# ETR_CELLMETER_SLAVE.net
KiCad netlist of a schematic drawn in Altium Designer
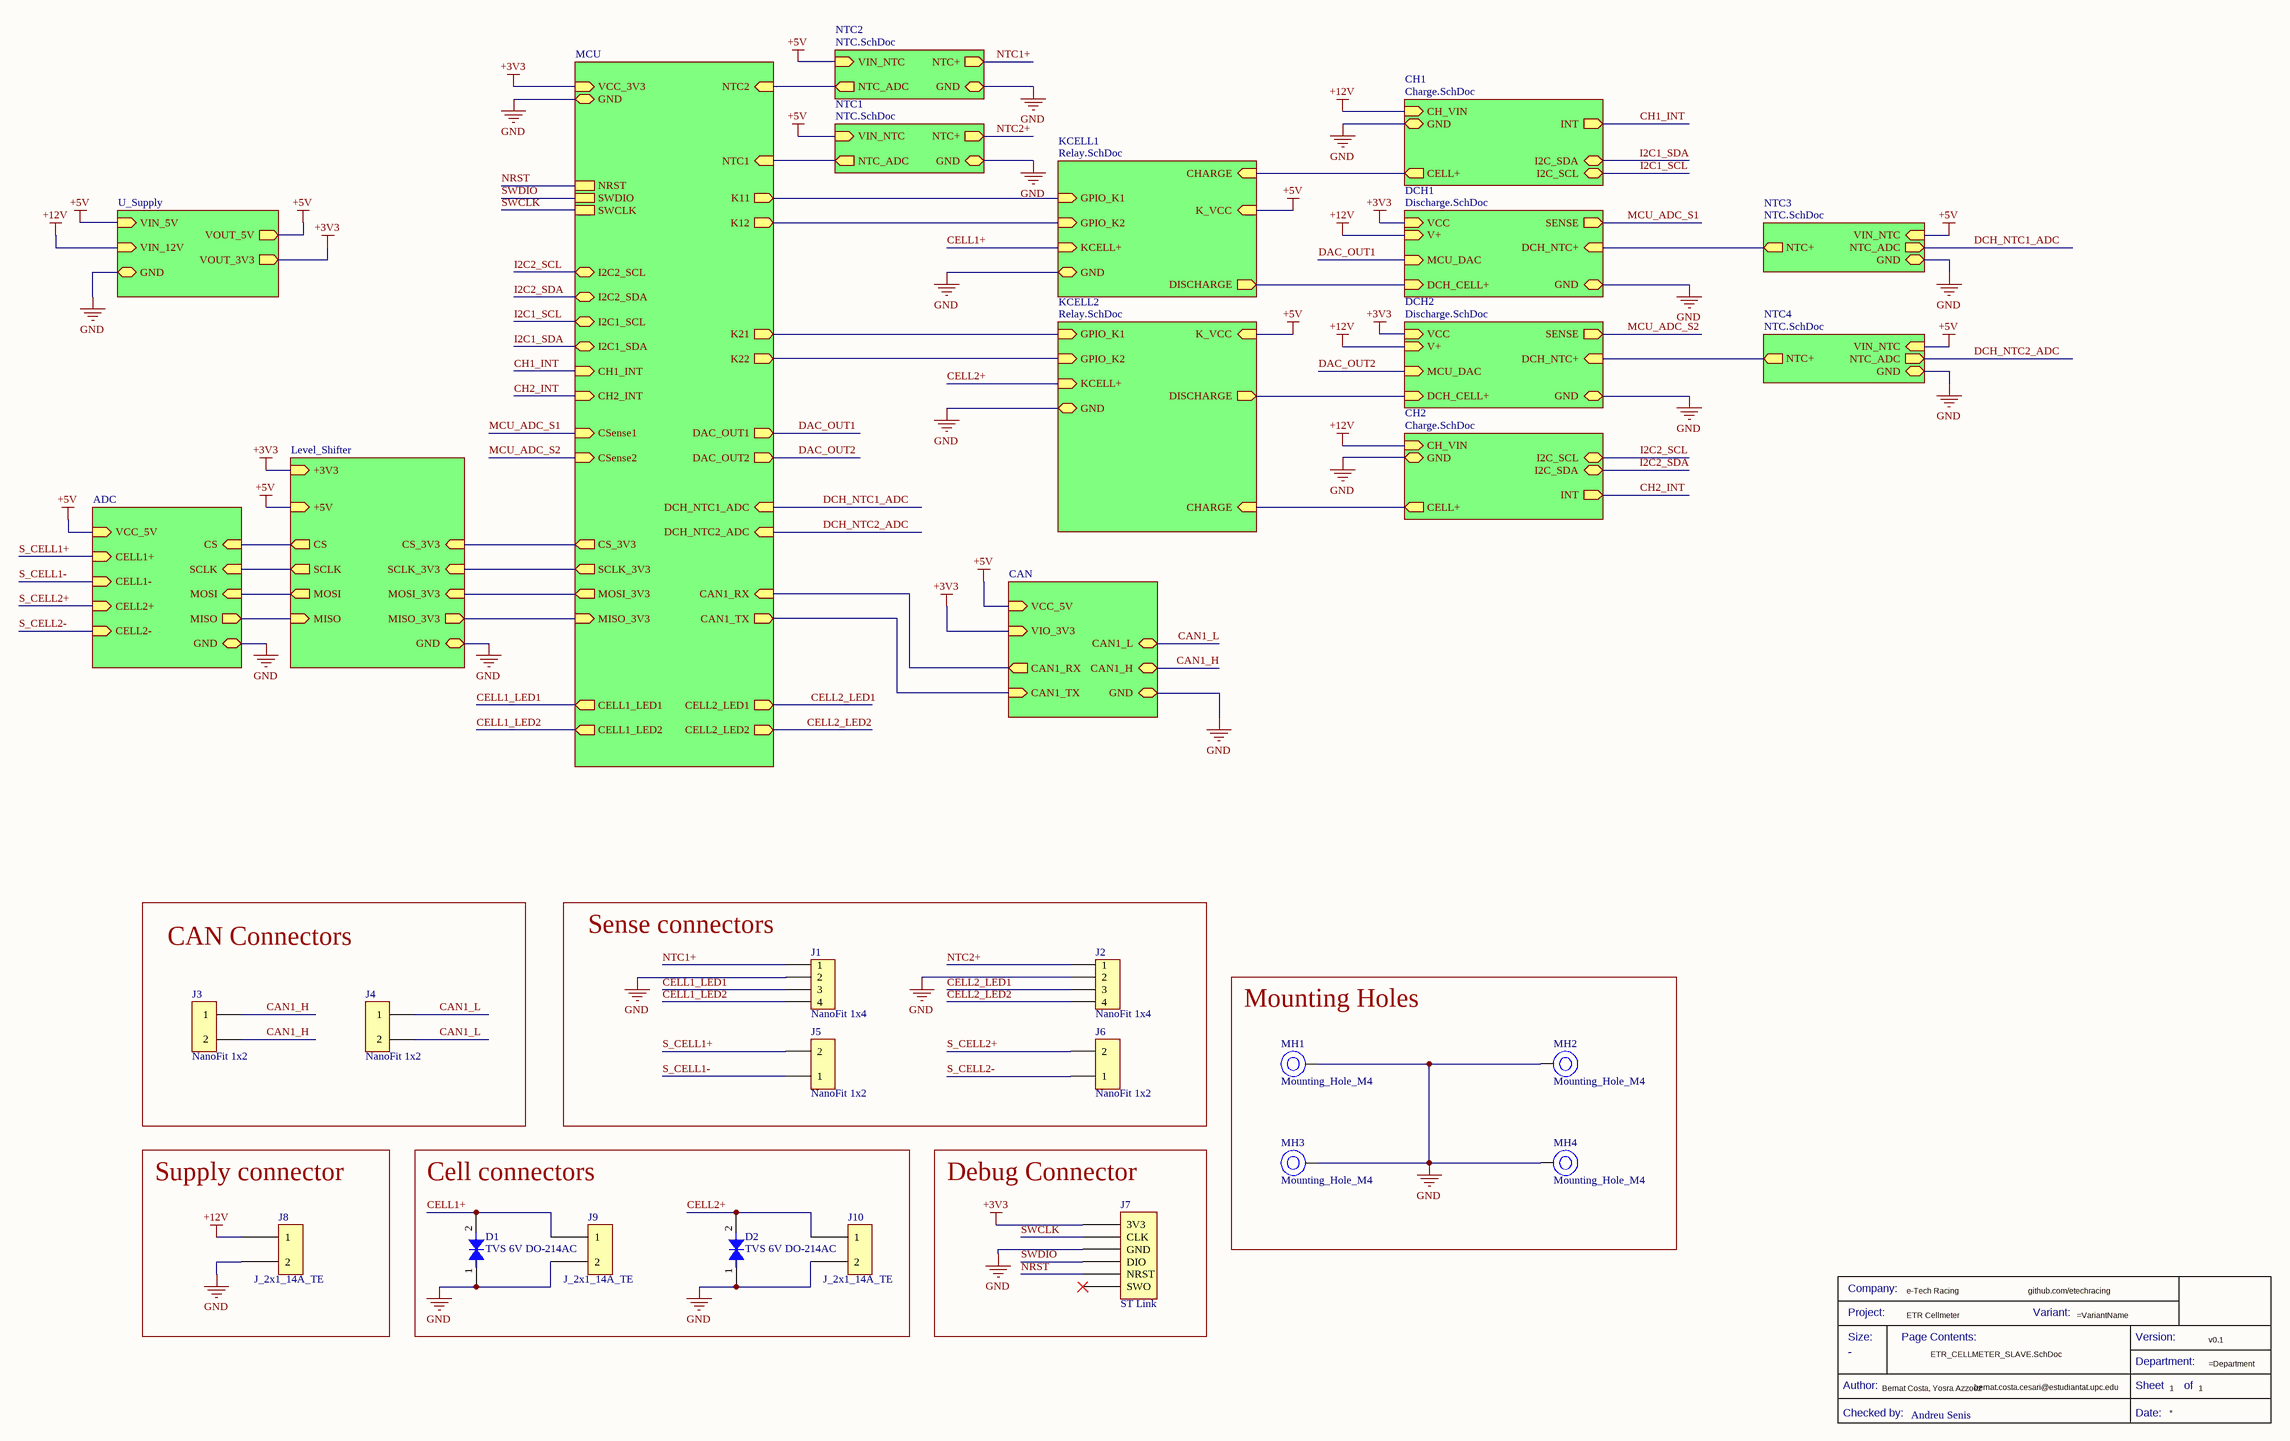
[diagram p0: ETR_CELLMETER_SLAVE.SchDoc]

(export (version "E")
  (design (tool "Eeschema 10.0.6"))
  (components
    (comp (ref "D1")
      (value "TVS 6V DO-214AC")
      (footprint "DTVS-DO-214AC")
      (description "TVS diode [Würth Elektronik] 824501600 TVS diode")
      (fields
        (field (name "MANUFACTURER") "Wurth Electronics")
        (field (name "MANUFACTURER PART NUMBER") "824501600")
        (field (name ".CREATOR") "DO")
      )
      (libsource (lib "EMEA- E-Tech Racing- I'Escola d'Enginyeria de Barcelona Est") (part "DTVS-BD-30k-SOD323"))
    )
    (comp (ref "D2")
      (value "TVS 6V DO-214AC")
      (footprint "DTVS-DO-214AC")
      (description "TVS diode [Würth Elektronik] 824501600 TVS diode")
      (fields
        (field (name "MANUFACTURER") "Wurth Electronics")
        (field (name "MANUFACTURER PART NUMBER") "824501600")
        (field (name ".CREATOR") "DO")
      )
      (libsource (lib "EMEA- E-Tech Racing- I'Escola d'Enginyeria de Barcelona Est") (part "DTVS-BD-30k-SOD323"))
    )
    (comp (ref "J1")
      (value "NanoFit 1x4")
      (footprint "J_NanoFit_1x4_V")
      (description "Nano-Fit Vertical Header Through Hole 2.50mm Pitch Single Row 4 Circuits with Kinked Pins 0.38")
      (fields (field (name ".CREATOR") "DO"))
      (libsource (lib "EMEA- E-Tech Racing- I'Escola d'Enginyeria de Barcelona Est") (part "J_NanoFit_1x4_V_W"))
    )
    (comp (ref "J2")
      (value "NanoFit 1x4")
      (footprint "J_NanoFit_1x4_V")
      (description "Nano-Fit Vertical Header Through Hole 2.50mm Pitch Single Row 4 Circuits with Kinked Pins 0.38")
      (fields (field (name ".CREATOR") "DO"))
      (libsource (lib "EMEA- E-Tech Racing- I'Escola d'Enginyeria de Barcelona Est") (part "J_NanoFit_1x4_V_W"))
    )
    (comp (ref "J3")
      (value "NanoFit 1x2")
      (footprint "FP-105309-1102-MFG")
      (description "Conn HDR 2 POS 2.5mm Solder ST Thru-Hole 2 Terminal 1 Port Nano-Fit Tray")
      (libsource (lib "EMEA- E-Tech Racing- I'Escola d'Enginyeria de Barcelona Est") (part "Molex Nano-Fit"))
    )
    (comp (ref "J4")
      (value "NanoFit 1x2")
      (footprint "FP-105309-1102-MFG")
      (description "Conn HDR 2 POS 2.5mm Solder ST Thru-Hole 2 Terminal 1 Port Nano-Fit Tray")
      (libsource (lib "EMEA- E-Tech Racing- I'Escola d'Enginyeria de Barcelona Est") (part "Molex Nano-Fit"))
    )
    (comp (ref "J5")
      (value "NanoFit 1x2")
      (footprint "FP-105309-1102-MFG")
      (description "Conn HDR 2 POS 2.5mm Solder ST Thru-Hole 2 Terminal 1 Port Nano-Fit Tray")
      (libsource (lib "") (part "Molex Nano-Fit_1"))
    )
    (comp (ref "J6")
      (value "NanoFit 1x2")
      (footprint "FP-105309-1102-MFG")
      (description "Conn HDR 2 POS 2.5mm Solder ST Thru-Hole 2 Terminal 1 Port Nano-Fit Tray")
      (libsource (lib "") (part "Molex Nano-Fit_1"))
    )
    (comp (ref "J7")
      (value "ST Link")
      (footprint "J_STLink_PinHeader")
      (libsource (lib "Electromechanical") (part "J_STLink_STM32_PinHeader_1x6"))
    )
    (comp (ref "J8")
      (value "J_2x1_14A_TE")
      (footprint "179838-2")
      (description "179838-2")
      (libsource (lib "EMEA- E-Tech Racing- I'Escola d'Enginyeria de Barcelona Est") (part "Power 2 pin connector"))
    )
    (comp (ref "J9")
      (value "J_2x1_14A_TE")
      (footprint "179838-2")
      (description "179838-2")
      (libsource (lib "EMEA- E-Tech Racing- I'Escola d'Enginyeria de Barcelona Est") (part "Power 2 pin connector"))
    )
    (comp (ref "J10")
      (value "J_2x1_14A_TE")
      (footprint "179838-2")
      (description "179838-2")
      (libsource (lib "EMEA- E-Tech Racing- I'Escola d'Enginyeria de Barcelona Est") (part "Power 2 pin connector"))
    )
    (comp (ref "MH1")
      (value "Mounting_Hole_M4")
      (footprint "Mounting_Hole_M4")
      (description "Mounting Hole M4")
      (libsource (lib "EMEA- E-Tech Racing- I'Escola d'Enginyeria de Barcelona Est") (part "Mounting_Hole_M4"))
    )
    (comp (ref "MH2")
      (value "Mounting_Hole_M4")
      (footprint "Mounting_Hole_M4")
      (description "Mounting Hole M4")
      (libsource (lib "EMEA- E-Tech Racing- I'Escola d'Enginyeria de Barcelona Est") (part "Mounting_Hole_M4"))
    )
    (comp (ref "MH3")
      (value "Mounting_Hole_M4")
      (footprint "Mounting_Hole_M4")
      (description "Mounting Hole M4")
      (libsource (lib "EMEA- E-Tech Racing- I'Escola d'Enginyeria de Barcelona Est") (part "Mounting_Hole_M4"))
    )
    (comp (ref "MH4")
      (value "Mounting_Hole_M4")
      (footprint "Mounting_Hole_M4")
      (description "Mounting Hole M4")
      (libsource (lib "EMEA- E-Tech Racing- I'Escola d'Enginyeria de Barcelona Est") (part "Mounting_Hole_M4"))
    )
  )
  (nets
    (net (code "1") (name "+3V3") (class "Default")
      (node (ref "J7") (pin "1") (pinfunction "3V3_1") (pintype "passive"))
    )
    (net (code "3") (name "+12V") (class "Default")
      (node (ref "J8") (pin "1") (pinfunction "1_1") (pintype "passive"))
    )
    (net (code "4") (name "/CAN1_H") (class "Default")
      (node (ref "J3") (pin "1") (pinfunction "1_1") (pintype "passive"))
      (node (ref "J3") (pin "2") (pinfunction "2_2") (pintype "passive"))
    )
    (net (code "5") (name "/CAN1_L") (class "Default")
      (node (ref "J4") (pin "1") (pinfunction "1_1") (pintype "passive"))
      (node (ref "J4") (pin "2") (pinfunction "2_2") (pintype "passive"))
    )
    (net (code "10") (name "/CELL1+") (class "Default")
      (node (ref "D1") (pin "2") (pinfunction "2_2") (pintype "passive"))
      (node (ref "J9") (pin "1") (pinfunction "1_1") (pintype "passive"))
    )
    (net (code "11") (name "/CELL1_LED1") (class "Default")
      (node (ref "J1") (pin "3") (pinfunction "3_3") (pintype "passive"))
    )
    (net (code "12") (name "/CELL1_LED2") (class "Default")
      (node (ref "J1") (pin "4") (pinfunction "4_4") (pintype "passive"))
    )
    (net (code "13") (name "/CELL2+") (class "Default")
      (node (ref "D2") (pin "2") (pinfunction "2_2") (pintype "passive"))
      (node (ref "J10") (pin "1") (pinfunction "1_1") (pintype "passive"))
    )
    (net (code "14") (name "/CELL2_LED1") (class "Default")
      (node (ref "J2") (pin "3") (pinfunction "3_3") (pintype "passive"))
    )
    (net (code "15") (name "/CELL2_LED2") (class "Default")
      (node (ref "J2") (pin "4") (pinfunction "4_4") (pintype "passive"))
    )
    (net (code "40") (name "/NRST") (class "Default")
      (node (ref "J7") (pin "5") (pinfunction "NRST_5") (pintype "passive"))
    )
    (net (code "43") (name "/NTC1+") (class "Default")
      (node (ref "J1") (pin "1") (pinfunction "1_1") (pintype "passive"))
    )
    (net (code "44") (name "/NTC2+") (class "Default")
      (node (ref "J2") (pin "1") (pinfunction "1_1") (pintype "passive"))
    )
    (net (code "49") (name "/SWCLK") (class "Default")
      (node (ref "J7") (pin "2") (pinfunction "CLK_2") (pintype "passive"))
    )
    (net (code "50") (name "/SWDIO") (class "Default")
      (node (ref "J7") (pin "4") (pinfunction "DIO_4") (pintype "passive"))
    )
    (net (code "51") (name "/S_CELL1+") (class "Default")
      (node (ref "J5") (pin "2") (pinfunction "2_2") (pintype "passive"))
    )
    (net (code "52") (name "/S_CELL1-") (class "Default")
      (node (ref "J5") (pin "1") (pinfunction "1_1") (pintype "passive"))
    )
    (net (code "53") (name "/S_CELL2+") (class "Default")
      (node (ref "J6") (pin "2") (pinfunction "2_2") (pintype "passive"))
    )
    (net (code "54") (name "/S_CELL2-") (class "Default")
      (node (ref "J6") (pin "1") (pinfunction "1_1") (pintype "passive"))
    )
    (net (code "55") (name "GND") (class "Default")
      (node (ref "D1") (pin "1") (pinfunction "1_1") (pintype "passive"))
      (node (ref "D2") (pin "1") (pinfunction "1_1") (pintype "passive"))
      (node (ref "J1") (pin "2") (pinfunction "2_2") (pintype "passive"))
      (node (ref "J10") (pin "2") (pinfunction "2_2") (pintype "passive"))
      (node (ref "J2") (pin "2") (pinfunction "2_2") (pintype "passive"))
      (node (ref "J7") (pin "3") (pinfunction "GND_3") (pintype "passive"))
      (node (ref "J8") (pin "2") (pinfunction "2_2") (pintype "passive"))
      (node (ref "J9") (pin "2") (pinfunction "2_2") (pintype "passive"))
      (node (ref "MH1") (pin "1") (pinfunction "1_1") (pintype "passive"))
      (node (ref "MH2") (pin "1") (pinfunction "1_1") (pintype "passive"))
      (node (ref "MH3") (pin "1") (pinfunction "1_1") (pintype "passive"))
      (node (ref "MH4") (pin "1") (pinfunction "1_1") (pintype "passive"))
    )
    (net (code "56") (name "unconnected-(J7-SWO-Pad6)") (class "Default")
      (node (ref "J7") (pin "6") (pinfunction "SWO_6") (pintype "passive+no_connect"))
    )
  )
)
